# NRF24l01.net
KiCad netlist of a schematic drawn in Altium Designer
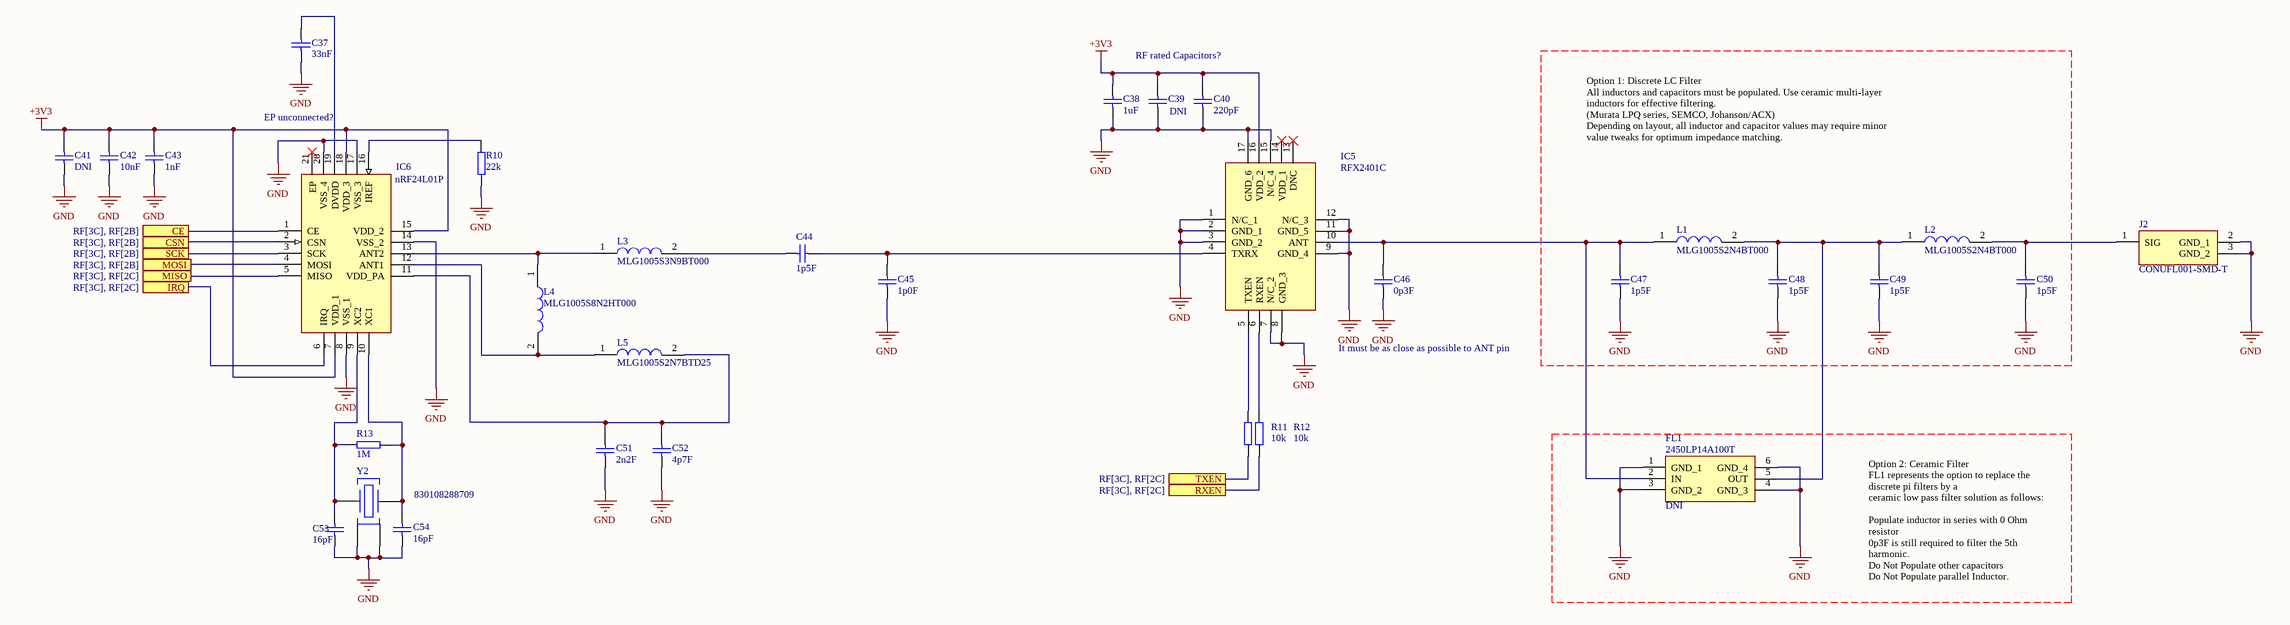
[diagram p0: NRF24l01.SchDoc]

(export (version "E")
  (design (tool "Eeschema 10.0.6"))
  (components
    (comp (ref "C37")
      (value "33nF")
      (footprint "CAP0402")
      (fields (field (name "VOLTAGE") "6V3") (field (name "Comment") "Cap0402"))
      (libsource (lib "capacitorsSMD") (part "Cap0402"))
    )
    (comp (ref "C38")
      (value "1uF")
      (footprint "CAP0402")
      (fields (field (name "VOLTAGE") "6V3") (field (name "Comment") "Cap0402"))
      (libsource (lib "capacitorsSMD") (part "Cap0402"))
    )
    (comp (ref "C39")
      (value "DNI")
      (footprint "CAP0402")
      (fields (field (name "VOLTAGE") "6V3") (field (name "Comment") "Cap0402"))
      (libsource (lib "capacitorsSMD") (part "Cap0402"))
    )
    (comp (ref "C40")
      (value "220pF")
      (footprint "CAP0402")
      (fields (field (name "VOLTAGE") "6V3") (field (name "Comment") "Cap0402"))
      (libsource (lib "capacitorsSMD") (part "Cap0402"))
    )
    (comp (ref "C41")
      (value "DNI")
      (footprint "CAP0402")
      (fields (field (name "VOLTAGE") "6V3") (field (name "Comment") "Cap0402"))
      (libsource (lib "capacitorsSMD") (part "Cap0402"))
    )
    (comp (ref "C42")
      (value "10nF")
      (footprint "CAP0402")
      (fields (field (name "VOLTAGE") "6V3") (field (name "Comment") "Cap0402"))
      (libsource (lib "capacitorsSMD") (part "Cap0402"))
    )
    (comp (ref "C43")
      (value "1nF")
      (footprint "CAP0402")
      (fields (field (name "VOLTAGE") "6V3") (field (name "Comment") "Cap0402"))
      (libsource (lib "capacitorsSMD") (part "Cap0402"))
    )
    (comp (ref "C44")
      (value "1p5F")
      (footprint "CAP0402")
      (description "RF NP0")
      (fields (field (name "VOLTAGE") "6V3") (field (name "Comment") "Cap0402"))
      (libsource (lib "capacitorsSMD") (part "Cap0402"))
    )
    (comp (ref "C45")
      (value "1p0F")
      (footprint "CAP0402")
      (description "RF NP0")
      (fields (field (name "VOLTAGE") "6V3") (field (name "Comment") "Cap0402"))
      (libsource (lib "capacitorsSMD") (part "Cap0402"))
    )
    (comp (ref "C46")
      (value "0p3F")
      (footprint "CAP0402")
      (description "RF NP0")
      (fields (field (name "VOLTAGE") "6V3") (field (name "Comment") "Cap0402"))
      (libsource (lib "capacitorsSMD") (part "Cap0402"))
    )
    (comp (ref "C47")
      (value "1p5F")
      (footprint "CAP0402")
      (description "RF NP0")
      (fields (field (name "VOLTAGE") "6V3") (field (name "Comment") "Cap0402"))
      (libsource (lib "capacitorsSMD") (part "Cap0402"))
    )
    (comp (ref "C48")
      (value "1p5F")
      (footprint "CAP0402")
      (description "RF NP0")
      (fields (field (name "VOLTAGE") "6V3") (field (name "Comment") "Cap0402"))
      (libsource (lib "capacitorsSMD") (part "Cap0402"))
    )
    (comp (ref "C49")
      (value "1p5F")
      (footprint "CAP0402")
      (description "RF NP0")
      (fields (field (name "VOLTAGE") "6V3") (field (name "Comment") "Cap0402"))
      (libsource (lib "capacitorsSMD") (part "Cap0402"))
    )
    (comp (ref "C50")
      (value "1p5F")
      (footprint "CAP0402")
      (description "RF NP0")
      (fields (field (name "VOLTAGE") "6V3") (field (name "Comment") "Cap0402"))
      (libsource (lib "capacitorsSMD") (part "Cap0402"))
    )
    (comp (ref "C51")
      (value "2n2F")
      (footprint "CAP0402")
      (description "RF NP0")
      (fields (field (name "VOLTAGE") "6V3") (field (name "Comment") "Cap0402"))
      (libsource (lib "capacitorsSMD") (part "Cap0402"))
    )
    (comp (ref "C52")
      (value "4p7F")
      (footprint "CAP0402")
      (description "RF NP0")
      (fields (field (name "VOLTAGE") "6V3") (field (name "Comment") "Cap0402"))
      (libsource (lib "capacitorsSMD") (part "Cap0402"))
    )
    (comp (ref "C53")
      (value "16pF")
      (footprint "CAP0402")
      (description "NP0")
      (fields (field (name "VOLTAGE") "6V3") (field (name "Comment") "Cap0402"))
      (libsource (lib "capacitorsSMD") (part "Cap0402"))
    )
    (comp (ref "C54")
      (value "16pF")
      (footprint "CAP0402")
      (description "NP0")
      (fields (field (name "VOLTAGE") "6V3") (field (name "Comment") "Cap0402"))
      (libsource (lib "capacitorsSMD") (part "Cap0402"))
    )
    (comp (ref "FL1")
      (value "2450LP14A100T")
      (footprint "SamacSys:2450LP14A100T")
      (description "Filter")
      (fields (field (name "ALTIUM_VALUE") "DNI"))
      (libsource (lib "*") (part "2450LP14A100T"))
    )
    (comp (ref "IC5")
      (value "RFX2401C")
      (footprint "SamacSys:QFN50P300X300X60-17N-D")
      (description "Integrated Circuit")
      (libsource (lib "*") (part "RFX2401C"))
    )
    (comp (ref "IC6")
      (value "nRF24L01P")
      (footprint "SamacSys:QFN50P400X400X95-21N-D")
      (description "Integrated Circuit")
      (libsource (lib "*") (part "nRF24L01P"))
    )
    (comp (ref "J2")
      (value "CONUFL001-SMD-T")
      (footprint "SamacSys:CONUFL001-SMD")
      (description "Connector")
      (fields (field (name "MOUSER PART NUMBER") "712-CONUFL001-SMD-T"))
      (libsource (lib "*") (part "CONUFL001-SMD-T"))
    )
    (comp (ref "L1")
      (value "MLG1005S2N4BT000")
      (footprint "SamacSys:MLG1005")
      (description "Inductor")
      (libsource (lib "*") (part "MLG1005S2N4BT000"))
    )
    (comp (ref "L2")
      (value "MLG1005S2N4BT000")
      (footprint "SamacSys:MLG1005")
      (description "Inductor")
      (libsource (lib "*") (part "MLG1005S2N4BT000"))
    )
    (comp (ref "L3")
      (value "MLG1005S3N9BT000")
      (footprint "SamacSys:MLG1005")
      (description "Inductor")
      (libsource (lib "*") (part "MLG1005S3N9BT000"))
    )
    (comp (ref "L4")
      (value "MLG1005S8N2HT000")
      (footprint "SamacSys:MLG1005")
      (description "Inductor")
      (libsource (lib "*") (part "MLG1005S8N2HT000"))
    )
    (comp (ref "L5")
      (value "MLG1005S2N7BTD25")
      (footprint "SamacSys:MLG1005")
      (description "Inductor")
      (libsource (lib "*") (part "MLG1005S2N7BTD25"))
    )
    (comp (ref "R10")
      (value "22k")
      (footprint "RES0402")
      (fields (field (name "Comment") "Res0402"))
      (libsource (lib "resistorSMD") (part "Res0402"))
    )
    (comp (ref "R11")
      (value "10k")
      (footprint "RES0402")
      (fields (field (name "Comment") "Res0402"))
      (libsource (lib "resistorSMD") (part "Res0402"))
    )
    (comp (ref "R12")
      (value "10k")
      (footprint "RES0402")
      (fields (field (name "Comment") "Res0402"))
      (libsource (lib "resistorSMD") (part "Res0402"))
    )
    (comp (ref "R13")
      (value "1M")
      (footprint "RES0402")
      (fields (field (name "Comment") "Res0402"))
      (libsource (lib "resistorSMD") (part "Res0402"))
    )
    (comp (ref "Y2")
      (value "830108288709")
      (footprint "SamacSys:830108288709")
      (description "Crystal or Oscillator")
      (libsource (lib "SamacSys") (part "830108288709"))
    )
  )
  (nets
    (net (code "1") (name "+3V3") (class "Default")
      (node (ref "C38") (pin "2") (pinfunction "2_2") (pintype "passive"))
      (node (ref "C39") (pin "2") (pinfunction "2_2") (pintype "passive"))
      (node (ref "C40") (pin "2") (pinfunction "2_2") (pintype "passive"))
      (node (ref "C41") (pin "2") (pinfunction "2_2") (pintype "passive"))
      (node (ref "C42") (pin "2") (pinfunction "2_2") (pintype "passive"))
      (node (ref "C43") (pin "2") (pinfunction "2_2") (pintype "passive"))
      (node (ref "IC5") (pin "16") (pinfunction "VDD_2_16") (pintype "passive"))
      (node (ref "IC6") (pin "15") (pinfunction "VDD_2_15") (pintype "power_in"))
      (node (ref "IC6") (pin "18") (pinfunction "VDD_3_18") (pintype "power_in"))
      (node (ref "IC6") (pin "7") (pinfunction "VDD_1_7") (pintype "power_in"))
    )
    (net (code "2") (name "/CE") (class "Default")
      (node (ref "IC6") (pin "1") (pinfunction "CE_1") (pintype "passive"))
    )
    (net (code "3") (name "/CSN") (class "Default")
      (node (ref "IC6") (pin "2") (pinfunction "CSN_2") (pintype "input"))
    )
    (net (code "4") (name "/IRQ") (class "Default")
      (node (ref "IC6") (pin "6") (pinfunction "IRQ_6") (pintype "passive"))
    )
    (net (code "5") (name "/MISO") (class "Default")
      (node (ref "IC6") (pin "5") (pinfunction "MISO_5") (pintype "passive"))
    )
    (net (code "6") (name "/MOSI") (class "Default")
      (node (ref "IC6") (pin "4") (pinfunction "MOSI_4") (pintype "passive"))
    )
    (net (code "7") (name "/RXEN") (class "Default")
      (node (ref "R12") (pin "1") (pinfunction "1_1") (pintype "passive"))
    )
    (net (code "8") (name "/SCK") (class "Default")
      (node (ref "IC6") (pin "3") (pinfunction "SCK_3") (pintype "passive"))
    )
    (net (code "9") (name "/TXEN") (class "Default")
      (node (ref "R11") (pin "1") (pinfunction "1_1") (pintype "passive"))
    )
    (net (code "10") (name "GND") (class "Default")
      (node (ref "C37") (pin "1") (pinfunction "1_1") (pintype "passive"))
      (node (ref "C38") (pin "1") (pinfunction "1_1") (pintype "passive"))
      (node (ref "C39") (pin "1") (pinfunction "1_1") (pintype "passive"))
      (node (ref "C40") (pin "1") (pinfunction "1_1") (pintype "passive"))
      (node (ref "C41") (pin "1") (pinfunction "1_1") (pintype "passive"))
      (node (ref "C42") (pin "1") (pinfunction "1_1") (pintype "passive"))
      (node (ref "C43") (pin "1") (pinfunction "1_1") (pintype "passive"))
      (node (ref "C45") (pin "1") (pinfunction "1_1") (pintype "passive"))
      (node (ref "C46") (pin "1") (pinfunction "1_1") (pintype "passive"))
      (node (ref "C47") (pin "1") (pinfunction "1_1") (pintype "passive"))
      (node (ref "C48") (pin "1") (pinfunction "1_1") (pintype "passive"))
      (node (ref "C49") (pin "1") (pinfunction "1_1") (pintype "passive"))
      (node (ref "C50") (pin "1") (pinfunction "1_1") (pintype "passive"))
      (node (ref "C51") (pin "1") (pinfunction "1_1") (pintype "passive"))
      (node (ref "C52") (pin "1") (pinfunction "1_1") (pintype "passive"))
      (node (ref "C53") (pin "1") (pinfunction "1_1") (pintype "passive"))
      (node (ref "C54") (pin "1") (pinfunction "1_1") (pintype "passive"))
      (node (ref "FL1") (pin "1") (pinfunction "GND_1_1") (pintype "passive"))
      (node (ref "FL1") (pin "3") (pinfunction "GND_2_3") (pintype "passive"))
      (node (ref "FL1") (pin "4") (pinfunction "GND_3_4") (pintype "passive"))
      (node (ref "FL1") (pin "6") (pinfunction "GND_4_6") (pintype "passive"))
      (node (ref "IC5") (pin "1") (pinfunction "N/C_1_1") (pintype "passive"))
      (node (ref "IC5") (pin "11") (pinfunction "GND_5_11") (pintype "passive"))
      (node (ref "IC5") (pin "12") (pinfunction "N/C_3_12") (pintype "passive"))
      (node (ref "IC5") (pin "15") (pinfunction "N/C_4_15") (pintype "passive"))
      (node (ref "IC5") (pin "17") (pinfunction "GND_6_17") (pintype "passive"))
      (node (ref "IC5") (pin "2") (pinfunction "GND_1_2") (pintype "passive"))
      (node (ref "IC5") (pin "3") (pinfunction "GND_2_3") (pintype "passive"))
      (node (ref "IC5") (pin "7") (pinfunction "N/C_2_7") (pintype "passive"))
      (node (ref "IC5") (pin "8") (pinfunction "GND_3_8") (pintype "passive"))
      (node (ref "IC5") (pin "9") (pinfunction "GND_4_9") (pintype "passive"))
      (node (ref "IC6") (pin "14") (pinfunction "VSS_2_14") (pintype "power_in"))
      (node (ref "IC6") (pin "17") (pinfunction "VSS_3_17") (pintype "power_in"))
      (node (ref "IC6") (pin "20") (pinfunction "VSS_4_20") (pintype "power_in"))
      (node (ref "IC6") (pin "8") (pinfunction "VSS_1_8") (pintype "power_in"))
      (node (ref "J2") (pin "2") (pinfunction "GND_1_2") (pintype "passive"))
      (node (ref "J2") (pin "3") (pinfunction "GND_2_3") (pintype "passive"))
      (node (ref "R10") (pin "1") (pinfunction "1_1") (pintype "passive"))
      (node (ref "Y2") (pin "2") (pinfunction "GND_1_2") (pintype "passive"))
      (node (ref "Y2") (pin "4") (pinfunction "GND_2_4") (pintype "passive"))
    )
    (net (code "11") (name "Net-(C44-Pad2)") (class "Default")
      (node (ref "C44") (pin "2") (pinfunction "2_2") (pintype "passive"))
      (node (ref "L3") (pin "2") (pinfunction "2_2") (pintype "passive"))
    )
    (net (code "12") (name "Net-(FL1-IN)") (class "Default")
      (node (ref "C46") (pin "2") (pinfunction "2_2") (pintype "passive"))
      (node (ref "C47") (pin "2") (pinfunction "2_2") (pintype "passive"))
      (node (ref "FL1") (pin "2") (pinfunction "IN_2") (pintype "passive"))
      (node (ref "IC5") (pin "10") (pinfunction "ANT_10") (pintype "passive"))
      (node (ref "L1") (pin "1") (pinfunction "1_1") (pintype "passive"))
    )
    (net (code "13") (name "Net-(FL1-OUT)") (class "Default")
      (node (ref "C48") (pin "2") (pinfunction "2_2") (pintype "passive"))
      (node (ref "C49") (pin "2") (pinfunction "2_2") (pintype "passive"))
      (node (ref "FL1") (pin "5") (pinfunction "OUT_5") (pintype "passive"))
      (node (ref "L1") (pin "2") (pinfunction "2_2") (pintype "passive"))
      (node (ref "L2") (pin "1") (pinfunction "1_1") (pintype "passive"))
    )
    (net (code "14") (name "Net-(IC5-RXEN)") (class "Default")
      (node (ref "IC5") (pin "6") (pinfunction "RXEN_6") (pintype "passive"))
      (node (ref "R12") (pin "2") (pinfunction "2_2") (pintype "passive"))
    )
    (net (code "15") (name "Net-(IC5-TXEN)") (class "Default")
      (node (ref "IC5") (pin "5") (pinfunction "TXEN_5") (pintype "passive"))
      (node (ref "R11") (pin "2") (pinfunction "2_2") (pintype "passive"))
    )
    (net (code "16") (name "Net-(IC5-TXRX)") (class "Default")
      (node (ref "C44") (pin "1") (pinfunction "1_1") (pintype "passive"))
      (node (ref "C45") (pin "2") (pinfunction "2_2") (pintype "passive"))
      (node (ref "IC5") (pin "4") (pinfunction "TXRX_4") (pintype "passive"))
    )
    (net (code "17") (name "Net-(IC6-ANT1)") (class "Default")
      (node (ref "IC6") (pin "12") (pinfunction "ANT1_12") (pintype "passive"))
      (node (ref "L4") (pin "2") (pinfunction "2_2") (pintype "passive"))
      (node (ref "L5") (pin "1") (pinfunction "1_1") (pintype "passive"))
    )
    (net (code "18") (name "Net-(IC6-ANT2)") (class "Default")
      (node (ref "IC6") (pin "13") (pinfunction "ANT2_13") (pintype "passive"))
      (node (ref "L3") (pin "1") (pinfunction "1_1") (pintype "passive"))
      (node (ref "L4") (pin "1") (pinfunction "1_1") (pintype "passive"))
    )
    (net (code "19") (name "Net-(IC6-DVDD)") (class "Default")
      (node (ref "C37") (pin "2") (pinfunction "2_2") (pintype "passive"))
      (node (ref "IC6") (pin "19") (pinfunction "DVDD_19") (pintype "power_in"))
    )
    (net (code "20") (name "Net-(IC6-IREF)") (class "Default")
      (node (ref "IC6") (pin "16") (pinfunction "IREF_16") (pintype "input"))
      (node (ref "R10") (pin "2") (pinfunction "2_2") (pintype "passive"))
    )
    (net (code "21") (name "Net-(IC6-VDD_PA)") (class "Default")
      (node (ref "C51") (pin "2") (pinfunction "2_2") (pintype "passive"))
      (node (ref "C52") (pin "2") (pinfunction "2_2") (pintype "passive"))
      (node (ref "IC6") (pin "11") (pinfunction "VDD_PA_11") (pintype "power_in"))
      (node (ref "L5") (pin "2") (pinfunction "2_2") (pintype "passive"))
    )
    (net (code "22") (name "Net-(IC6-XC1)") (class "Default")
      (node (ref "C54") (pin "2") (pinfunction "2_2") (pintype "passive"))
      (node (ref "IC6") (pin "10") (pinfunction "XC1_10") (pintype "passive"))
      (node (ref "R13") (pin "2") (pinfunction "2_2") (pintype "passive"))
      (node (ref "Y2") (pin "3") (pinfunction "CRYSTAL_2_3") (pintype "passive"))
    )
    (net (code "23") (name "Net-(IC6-XC2)") (class "Default")
      (node (ref "C53") (pin "2") (pinfunction "2_2") (pintype "passive"))
      (node (ref "IC6") (pin "9") (pinfunction "XC2_9") (pintype "passive"))
      (node (ref "R13") (pin "1") (pinfunction "1_1") (pintype "passive"))
      (node (ref "Y2") (pin "1") (pinfunction "CRYSTAL_1_1") (pintype "passive"))
    )
    (net (code "24") (name "Net-(J2-SIG)") (class "Default")
      (node (ref "C50") (pin "2") (pinfunction "2_2") (pintype "passive"))
      (node (ref "J2") (pin "1") (pinfunction "SIG_1") (pintype "passive"))
      (node (ref "L2") (pin "2") (pinfunction "2_2") (pintype "passive"))
    )
    (net (code "25") (name "unconnected-(IC5-DNC-Pad13)") (class "Default")
      (node (ref "IC5") (pin "13") (pinfunction "DNC_13") (pintype "passive+no_connect"))
    )
    (net (code "26") (name "unconnected-(IC5-VDD_1-Pad14)") (class "Default")
      (node (ref "IC5") (pin "14") (pinfunction "VDD_1_14") (pintype "passive+no_connect"))
    )
    (net (code "27") (name "unconnected-(IC6-EP-Pad21)") (class "Default")
      (node (ref "IC6") (pin "21") (pinfunction "EP_21") (pintype "passive+no_connect"))
    )
  )
)
